# Heater_Cal_Laser.net
KiCad netlist of a schematic drawn in Altium Designer
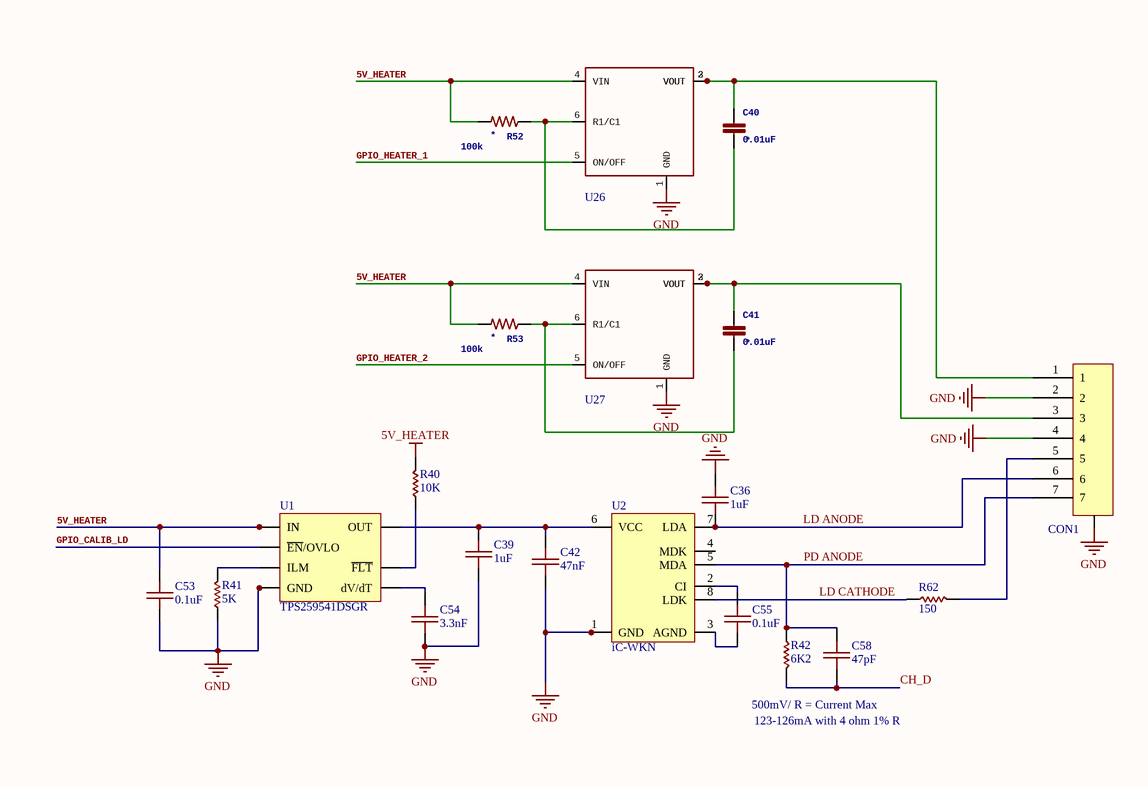
[diagram p0: Heater & Cal. Laser.SchDoc]

(export (version "E")
  (design (tool "Eeschema 10.0.6"))
  (components
    (comp (ref "C36")
      (value "1uF")
      (footprint "0402 B")
      (description "402 Capacitor")
      (libsource (lib "DaughterBoard") (part "CAP 0402"))
    )
    (comp (ref "C39")
      (value "1uF")
      (footprint "0402 B")
      (description "402 Capacitor")
      (libsource (lib "DaughterBoard") (part "CAP 0402"))
    )
    (comp (ref "C40")
      (value "0.01uF")
      (footprint "0603")
      (description "CAPACITOR, European symbol")
      (fields (field (name "NAME") "*"))
      (libsource (lib "rcl") (part "C-EUC0603K"))
    )
    (comp (ref "C41")
      (value "0.01uF")
      (footprint "0603")
      (description "CAPACITOR, European symbol")
      (fields (field (name "NAME") "*"))
      (libsource (lib "rcl") (part "C-EUC0603K"))
    )
    (comp (ref "C42")
      (value "47nF")
      (footprint "0402 B")
      (description "402 Capacitor")
      (libsource (lib "DaughterBoard") (part "CAP 0402"))
    )
    (comp (ref "C53")
      (value "0.1uF")
      (footprint "0402 B")
      (description "402 Capacitor")
      (libsource (lib "DaughterBoard") (part "CAP 0402"))
    )
    (comp (ref "C54")
      (value "3.3nF")
      (footprint "0402 B")
      (description "402 Capacitor")
      (libsource (lib "DaughterBoard") (part "CAP 0402"))
    )
    (comp (ref "C55")
      (value "0.1uF")
      (footprint "0402 B")
      (description "402 Capacitor")
      (libsource (lib "DaughterBoard") (part "CAP 0402"))
    )
    (comp (ref "C58")
      (value "47pF")
      (footprint "0402 B")
      (description "402 Capacitor")
      (libsource (lib "DaughterBoard") (part "CAP 0402"))
    )
    (comp (ref "CON1")
      (value "T1M-07-F-SH-L-K_1")
      (footprint "T1M-07-F-SH-L-K")
      (description "6 Positions Header Connector Surface Mount, Right Angle")
      (fields
        (field (name "MANUFACTURER") "Samtec")
        (field (name "MANUFACTURER PART NUMBER") "T1M-06-F-SH-L-K")
      )
      (libsource (lib "DaughterBoard") (part "T1M-07-F-SH-L-K_1"))
    )
    (comp (ref "R40")
      (value "10K")
      (footprint "0402")
      (description "402 Resistor")
      (libsource (lib "UNP2") (part "RES 0402"))
    )
    (comp (ref "R41")
      (value "5K")
      (footprint "0402")
      (description "402 Resistor")
      (libsource (lib "UNP2") (part "RES 0402"))
    )
    (comp (ref "R42")
      (value "6K2")
      (footprint "0402R")
      (description "402 Resistor")
      (libsource (lib "DaughterBoard") (part "RES 0402"))
    )
    (comp (ref "R52")
      (value "100k")
      (footprint "0603R")
      (description "RESISTOR, American symbol")
      (fields (field (name "NAME") "*"))
      (libsource (lib "rcl") (part "R-US_R0603"))
    )
    (comp (ref "R53")
      (value "100k")
      (footprint "0603R")
      (description "RESISTOR, American symbol")
      (fields (field (name "NAME") "*"))
      (libsource (lib "rcl") (part "R-US_R0603"))
    )
    (comp (ref "R62")
      (value "150")
      (footprint "0402R")
      (description "402 Resistor")
      (libsource (lib "DaughterBoard") (part "RES 0402"))
    )
    (comp (ref "U1")
      (value "TPS259541DSGR")
      (footprint "SON8 (2x2)")
      (libsource (lib "DaughterBoard") (part "TPS2595x3"))
    )
    (comp (ref "U2") (value "iC-WKN") (footprint "SOIC8tp") (libsource (lib "DaughterBoard") (part "iC-WKN")))
    (comp (ref "U26")
      (value "TPS27082L")
      (footprint "TSOT-23 6 Lead")
      (libsource (lib "custom") (part "TPS27082L"))
    )
    (comp (ref "U27")
      (value "TPS27082L")
      (footprint "TSOT-23 6 Lead")
      (libsource (lib "custom") (part "TPS27082L"))
    )
  )
  (nets
    (net (code "1") (name "/CH_D") (class "Default")
      (node (ref "C58") (pin "1") (pintype "passive"))
      (node (ref "R42") (pin "1") (pintype "passive"))
    )
    (net (code "2") (name "/GPIO_CALIB_LD") (class "Default")
      (node (ref "U1") (pin "2") (pinfunction "~{EN}/OVLO_2") (pintype "passive"))
    )
    (net (code "3") (name "/GPIO_HEATER_1") (class "Default")
      (node (ref "U26") (pin "5") (pinfunction "ON/OFF_5") (pintype "passive"))
    )
    (net (code "4") (name "/GPIO_HEATER_2") (class "Default")
      (node (ref "U27") (pin "5") (pinfunction "ON/OFF_5") (pintype "passive"))
    )
    (net (code "5") (name "/LD ANODE") (class "Default")
      (node (ref "C36") (pin "1") (pintype "passive"))
      (node (ref "CON1") (pin "6") (pinfunction "6_6") (pintype "passive"))
      (node (ref "U2") (pin "7") (pinfunction "LDA_7") (pintype "passive"))
    )
    (net (code "6") (name "/LD CATHODE") (class "Default")
      (node (ref "R62") (pin "2") (pintype "passive"))
      (node (ref "U2") (pin "8") (pinfunction "LDK_8") (pintype "passive"))
    )
    (net (code "7") (name "/PD ANODE") (class "Default")
      (node (ref "C58") (pin "2") (pintype "passive"))
      (node (ref "CON1") (pin "7") (pinfunction "7_7") (pintype "passive"))
      (node (ref "R42") (pin "2") (pintype "passive"))
      (node (ref "U2") (pin "5") (pinfunction "MDA_5") (pintype "passive"))
    )
    (net (code "8") (name "5V_HEATER") (class "Default")
      (node (ref "C53") (pin "2") (pintype "passive"))
      (node (ref "R40") (pin "1") (pintype "passive"))
      (node (ref "R52") (pin "2") (pinfunction "2_2") (pintype "passive"))
      (node (ref "R53") (pin "2") (pinfunction "2_2") (pintype "passive"))
      (node (ref "U1") (pin "3") (pinfunction "IN_3") (pintype "passive"))
      (node (ref "U1") (pin "4") (pinfunction "IN_4") (pintype "passive"))
      (node (ref "U26") (pin "4") (pinfunction "VIN_4") (pintype "passive"))
      (node (ref "U27") (pin "4") (pinfunction "VIN_4") (pintype "passive"))
    )
    (net (code "9") (name "GND") (class "Default")
      (node (ref "C36") (pin "2") (pintype "passive"))
      (node (ref "C39") (pin "1") (pintype "passive"))
      (node (ref "C42") (pin "1") (pintype "passive"))
      (node (ref "C53") (pin "1") (pintype "passive"))
      (node (ref "C54") (pin "1") (pintype "passive"))
      (node (ref "CON1") (pin "2") (pinfunction "2_2") (pintype "passive"))
      (node (ref "CON1") (pin "4") (pinfunction "4_4") (pintype "passive"))
      (node (ref "CON1") (pin "GND") (pinfunction "GND_GND") (pintype "passive"))
      (node (ref "R41") (pin "2") (pintype "passive"))
      (node (ref "U1") (pin "8") (pinfunction "GND_8") (pintype "passive"))
      (node (ref "U1") (pin "9") (pintype "passive"))
      (node (ref "U2") (pin "1") (pinfunction "GND_1") (pintype "passive"))
      (node (ref "U2") (pin "9") (pintype "passive"))
      (node (ref "U26") (pin "1") (pinfunction "GND_1") (pintype "passive"))
      (node (ref "U27") (pin "1") (pinfunction "GND_1") (pintype "passive"))
    )
    (net (code "10") (name "Net-(C40-Pad1)") (class "Default")
      (node (ref "C40") (pin "1") (pinfunction "1_1") (pintype "passive"))
      (node (ref "CON1") (pin "1") (pinfunction "1_1") (pintype "passive"))
      (node (ref "U26") (pin "2") (pinfunction "VOUT_2") (pintype "passive"))
      (node (ref "U26") (pin "3") (pinfunction "VOUT_3") (pintype "passive"))
    )
    (net (code "11") (name "Net-(C41-Pad1)") (class "Default")
      (node (ref "C41") (pin "1") (pinfunction "1_1") (pintype "passive"))
      (node (ref "CON1") (pin "3") (pinfunction "3_3") (pintype "passive"))
      (node (ref "U27") (pin "2") (pinfunction "VOUT_2") (pintype "passive"))
      (node (ref "U27") (pin "3") (pinfunction "VOUT_3") (pintype "passive"))
    )
    (net (code "12") (name "Net-(CON1-Pad5)") (class "Default")
      (node (ref "CON1") (pin "5") (pinfunction "5_5") (pintype "passive"))
      (node (ref "R62") (pin "1") (pintype "passive"))
    )
    (net (code "13") (name "Net-(U1-ILM)") (class "Default")
      (node (ref "R41") (pin "1") (pintype "passive"))
      (node (ref "U1") (pin "7") (pinfunction "ILM_7") (pintype "passive"))
    )
    (net (code "14") (name "Net-(U1-OUT)") (class "Default")
      (node (ref "C39") (pin "2") (pintype "passive"))
      (node (ref "C42") (pin "2") (pintype "passive"))
      (node (ref "U1") (pin "5") (pinfunction "OUT_5") (pintype "passive"))
      (node (ref "U2") (pin "6") (pinfunction "VCC_6") (pintype "passive"))
    )
    (net (code "15") (name "Net-(U1-dV{slash}dT)") (class "Default")
      (node (ref "C54") (pin "2") (pintype "passive"))
      (node (ref "U1") (pin "1") (pinfunction "dV/dT_1") (pintype "passive"))
    )
    (net (code "16") (name "Net-(U1-~{FLT})") (class "Default")
      (node (ref "R40") (pin "2") (pintype "passive"))
      (node (ref "U1") (pin "6") (pinfunction "~{FLT}_6") (pintype "passive"))
    )
    (net (code "17") (name "Net-(U2-AGND)") (class "Default")
      (node (ref "C55") (pin "1") (pintype "passive"))
      (node (ref "U2") (pin "3") (pinfunction "AGND_3") (pintype "passive"))
    )
    (net (code "18") (name "Net-(U2-CI)") (class "Default")
      (node (ref "C55") (pin "2") (pintype "passive"))
      (node (ref "U2") (pin "2") (pinfunction "CI_2") (pintype "passive"))
    )
    (net (code "19") (name "Net-(U26-R1{slash}C1)") (class "Default")
      (node (ref "C40") (pin "2") (pinfunction "2_2") (pintype "passive"))
      (node (ref "R52") (pin "1") (pinfunction "1_1") (pintype "passive"))
      (node (ref "U26") (pin "6") (pinfunction "R1/C1_6") (pintype "passive"))
    )
    (net (code "20") (name "Net-(U27-R1{slash}C1)") (class "Default")
      (node (ref "C41") (pin "2") (pinfunction "2_2") (pintype "passive"))
      (node (ref "R53") (pin "1") (pinfunction "1_1") (pintype "passive"))
      (node (ref "U27") (pin "6") (pinfunction "R1/C1_6") (pintype "passive"))
    )
    (net (code "21") (name "unconnected-(U2-MDK-Pad4)") (class "Default")
      (node (ref "U2") (pin "4") (pinfunction "MDK_4") (pintype "passive"))
    )
  )
)
